# TempSensor.net
KiCad netlist of a schematic drawn in Altium Designer
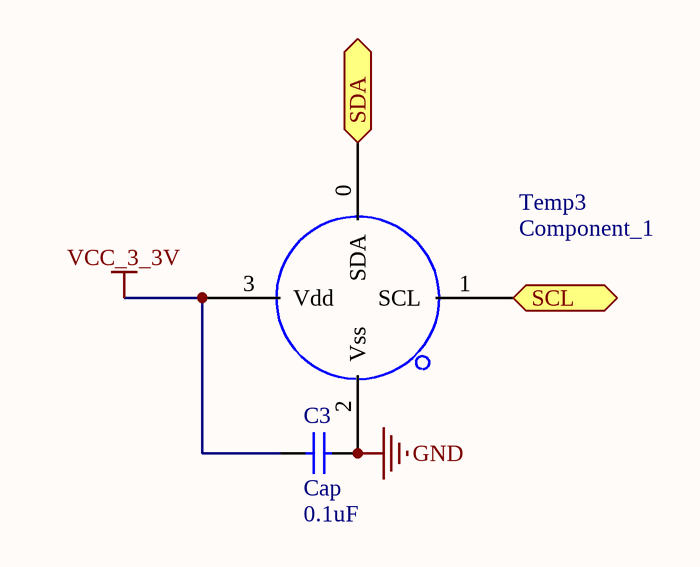
[diagram p0: TempSensor.SchDoc]

(export (version "E")
  (design (tool "Eeschema 10.0.6"))
  (components
    (comp (ref "C3")
      (value "Cap")
      (footprint "R0805")
      (description "Capacitor")
      (fields (field (name "ALTIUM_VALUE") "0.1uF") (field (name "PUBLISHER") "Altium Limited"))
      (libsource (lib "Miscellaneous Devices") (part "Cap"))
    )
    (comp (ref "Temp3")
      (value "Component_1")
      (footprint "MLX90614")
      (libsource (lib "MLX90614ESFACA") (part "Component_1"))
    )
  )
  (nets
    (net (code "1") (name "/SCL") (class "Default")
      (node (ref "Temp3") (pin "1") (pinfunction "SCL_1") (pintype "passive"))
    )
    (net (code "2") (name "/SDA") (class "Default")
      (node (ref "Temp3") (pin "0") (pinfunction "SDA_0") (pintype "passive"))
    )
    (net (code "3") (name "GND") (class "Default")
      (node (ref "C3") (pin "2") (pinfunction "2_2") (pintype "passive"))
      (node (ref "Temp3") (pin "2") (pinfunction "Vss_2") (pintype "power_in"))
    )
    (net (code "4") (name "VCC_3_3V") (class "Default")
      (node (ref "C3") (pin "1") (pinfunction "1_1") (pintype "passive"))
      (node (ref "Temp3") (pin "3") (pinfunction "Vdd_3") (pintype "power_in"))
    )
  )
)
